# eib-generic.net
KiCad netlist of a schematic drawn in EAGLE
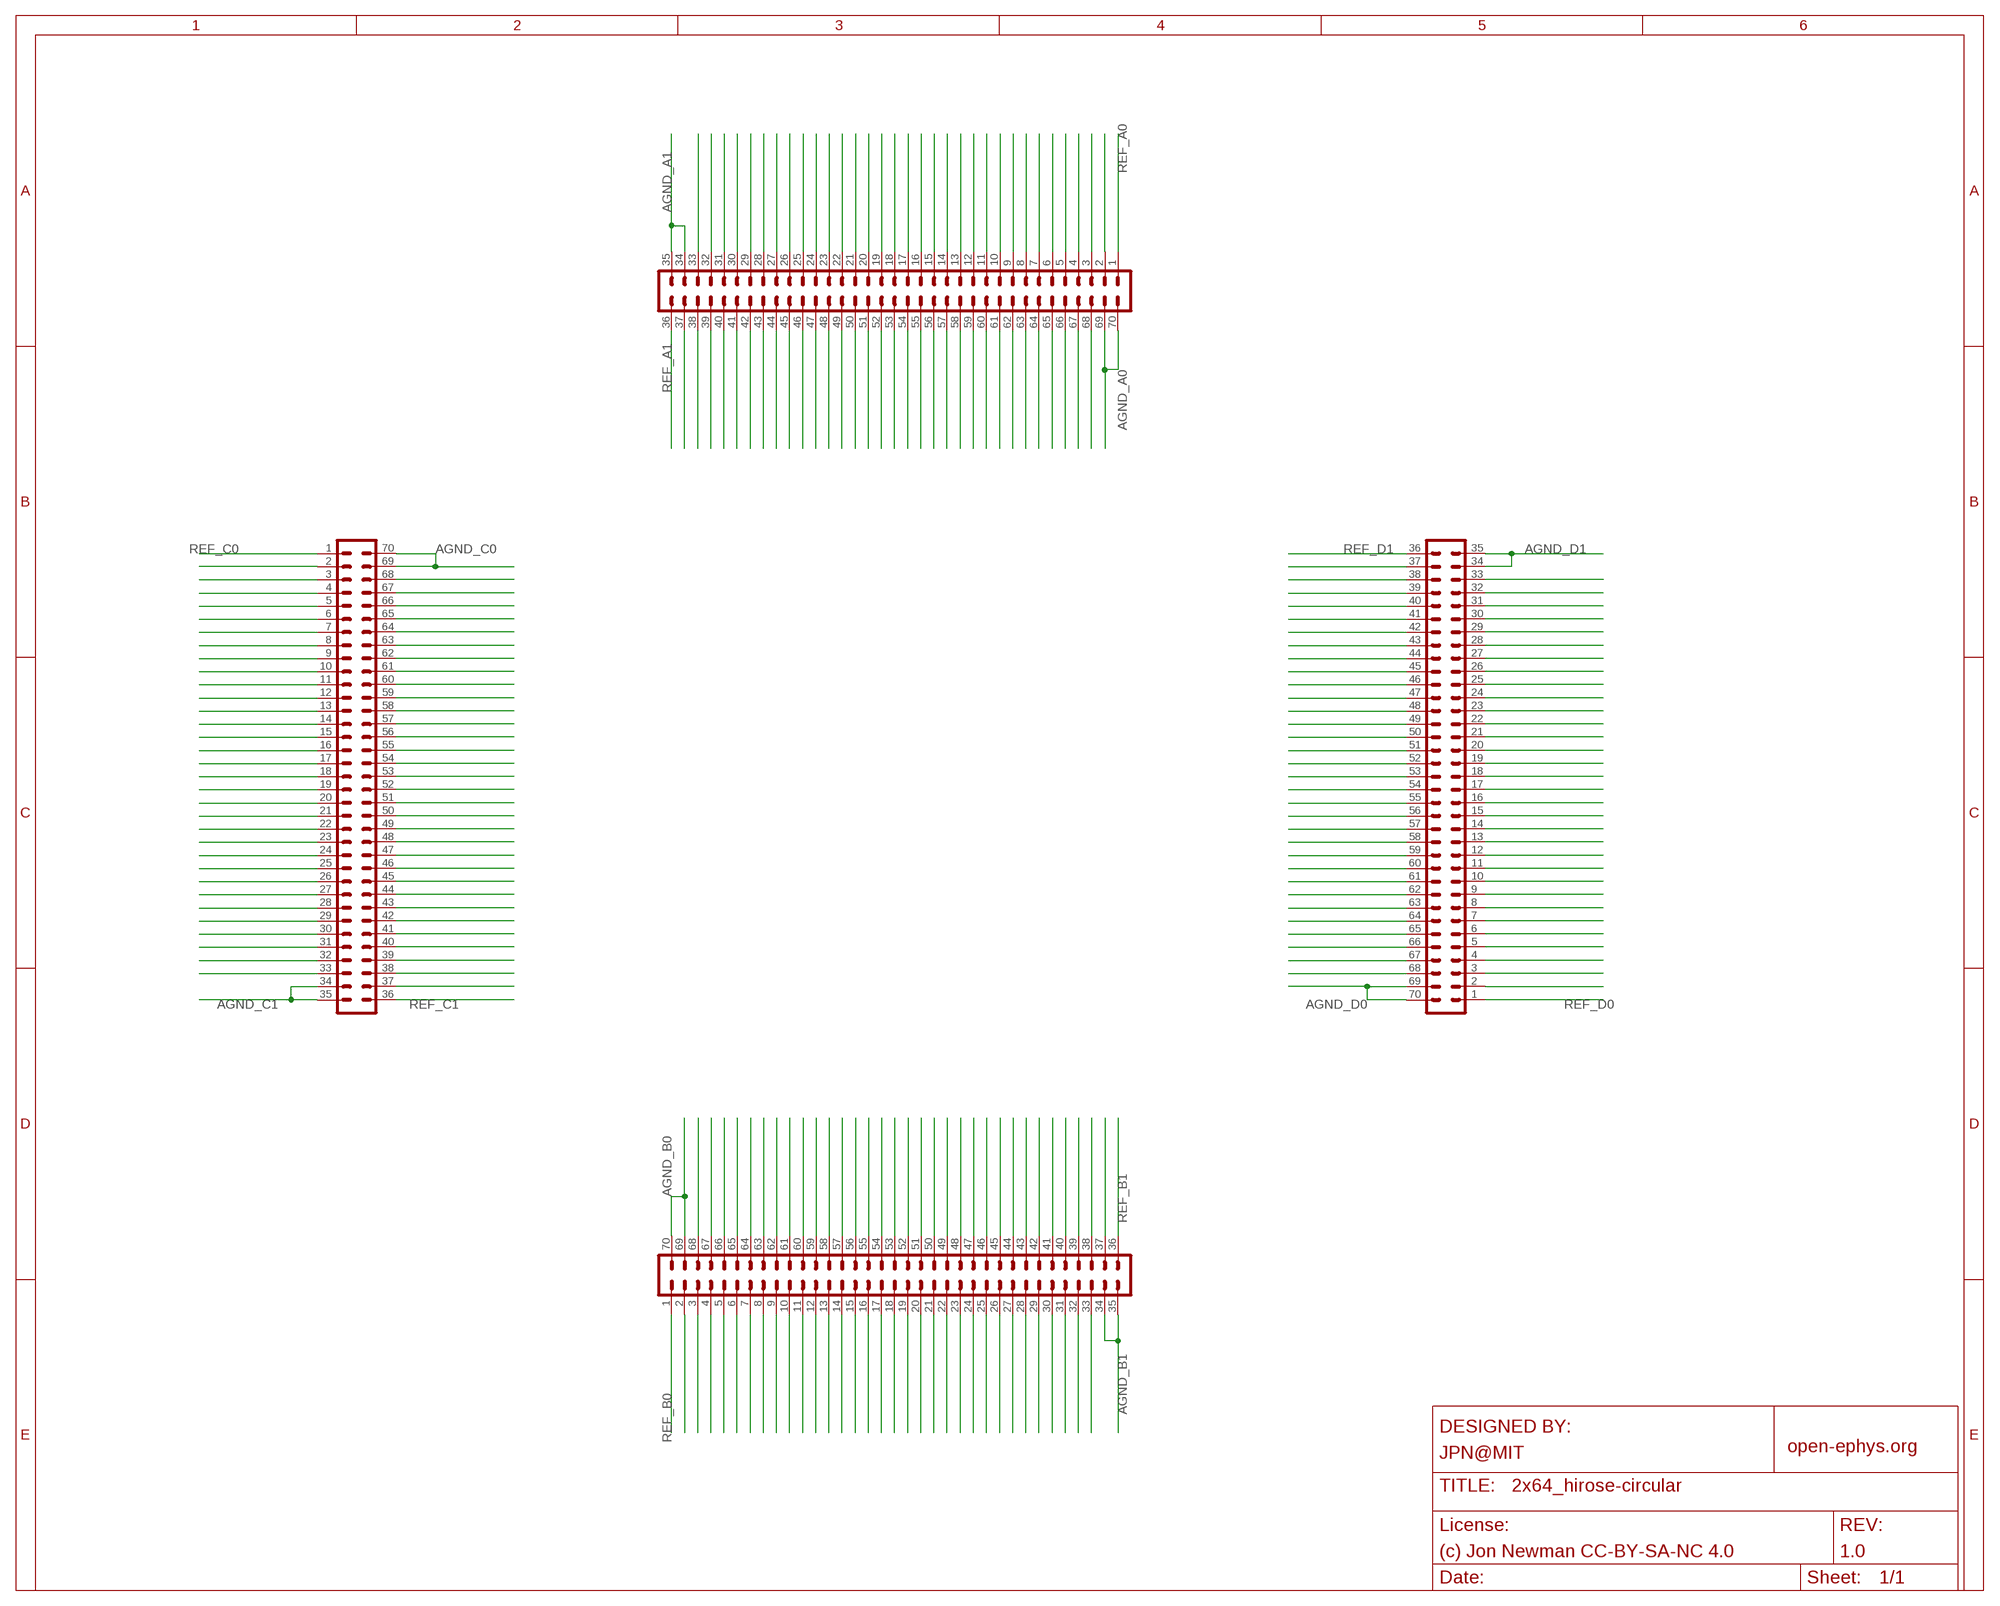
[diagram p0: schematic, sheet 1]

(export (version "E")
  (design (tool "Eeschema 10.0.6"))
  (components
    (comp (ref "A")
      (value "DF40HEAD")
      (footprint "eagle-import:DF40-70HEAD")
      (libsource (lib "eagle-import") (part "PINHD-2X35_DF40HEAD"))
    )
    (comp (ref "B")
      (value "DF40HEAD")
      (footprint "eagle-import:DF40-70HEAD")
      (libsource (lib "eagle-import") (part "PINHD-2X35_DF40HEAD"))
    )
    (comp (ref "C")
      (value "DF40HEAD")
      (footprint "eagle-import:DF40-70HEAD")
      (libsource (lib "eagle-import") (part "PINHD-2X35_DF40HEAD"))
    )
    (comp (ref "D")
      (value "DF40HEAD")
      (footprint "eagle-import:DF40-70HEAD")
      (libsource (lib "eagle-import") (part "PINHD-2X35_DF40HEAD"))
    )
  )
  (nets
    (net (code "1") (name "/AGND_A0") (class "Default")
      (node (ref "A") (pin "69") (pinfunction "69_69") (pintype "bidirectional"))
      (node (ref "A") (pin "70") (pinfunction "70_70") (pintype "bidirectional"))
    )
    (net (code "2") (name "/AGND_A1") (class "Default")
      (node (ref "A") (pin "34") (pinfunction "34_34") (pintype "bidirectional"))
      (node (ref "A") (pin "35") (pinfunction "35_35") (pintype "bidirectional"))
    )
    (net (code "3") (name "/AGND_B0") (class "Default")
      (node (ref "B") (pin "69") (pinfunction "69_69") (pintype "bidirectional"))
      (node (ref "B") (pin "70") (pinfunction "70_70") (pintype "bidirectional"))
    )
    (net (code "4") (name "/AGND_B1") (class "Default")
      (node (ref "B") (pin "34") (pinfunction "34_34") (pintype "bidirectional"))
      (node (ref "B") (pin "35") (pinfunction "35_35") (pintype "bidirectional"))
    )
    (net (code "5") (name "/AGND_C0") (class "Default")
      (node (ref "C") (pin "69") (pinfunction "69_69") (pintype "bidirectional"))
      (node (ref "C") (pin "70") (pinfunction "70_70") (pintype "bidirectional"))
    )
    (net (code "6") (name "/AGND_C1") (class "Default")
      (node (ref "C") (pin "34") (pinfunction "34_34") (pintype "bidirectional"))
      (node (ref "C") (pin "35") (pinfunction "35_35") (pintype "bidirectional"))
    )
    (net (code "7") (name "/AGND_D0") (class "Default")
      (node (ref "D") (pin "69") (pinfunction "69_69") (pintype "bidirectional"))
      (node (ref "D") (pin "70") (pinfunction "70_70") (pintype "bidirectional"))
    )
    (net (code "8") (name "/AGND_D1") (class "Default")
      (node (ref "D") (pin "34") (pinfunction "34_34") (pintype "bidirectional"))
      (node (ref "D") (pin "35") (pinfunction "35_35") (pintype "bidirectional"))
    )
    (net (code "9") (name "/REF_A0") (class "Default")
      (node (ref "A") (pin "1") (pinfunction "1_1") (pintype "bidirectional"))
    )
    (net (code "10") (name "/REF_A1") (class "Default")
      (node (ref "A") (pin "36") (pinfunction "36_36") (pintype "bidirectional"))
    )
    (net (code "11") (name "/REF_B0") (class "Default")
      (node (ref "B") (pin "1") (pinfunction "1_1") (pintype "bidirectional"))
    )
    (net (code "12") (name "/REF_B1") (class "Default")
      (node (ref "B") (pin "36") (pinfunction "36_36") (pintype "bidirectional"))
    )
    (net (code "13") (name "/REF_C0") (class "Default")
      (node (ref "C") (pin "1") (pinfunction "1_1") (pintype "bidirectional"))
    )
    (net (code "14") (name "/REF_C1") (class "Default")
      (node (ref "C") (pin "36") (pinfunction "36_36") (pintype "bidirectional"))
    )
    (net (code "15") (name "/REF_D0") (class "Default")
      (node (ref "D") (pin "1") (pinfunction "1_1") (pintype "bidirectional"))
    )
    (net (code "16") (name "/REF_D1") (class "Default")
      (node (ref "D") (pin "36") (pinfunction "36_36") (pintype "bidirectional"))
    )
    (net (code "17") (name "unconnected-(A-Pad2)") (class "Default")
      (node (ref "A") (pin "2") (pinfunction "2_2") (pintype "bidirectional"))
    )
    (net (code "18") (name "unconnected-(A-Pad3)") (class "Default")
      (node (ref "A") (pin "3") (pinfunction "3_3") (pintype "bidirectional"))
    )
    (net (code "19") (name "unconnected-(A-Pad4)") (class "Default")
      (node (ref "A") (pin "4") (pinfunction "4_4") (pintype "bidirectional"))
    )
    (net (code "20") (name "unconnected-(A-Pad5)") (class "Default")
      (node (ref "A") (pin "5") (pinfunction "5_5") (pintype "bidirectional"))
    )
    (net (code "21") (name "unconnected-(A-Pad6)") (class "Default")
      (node (ref "A") (pin "6") (pinfunction "6_6") (pintype "bidirectional"))
    )
    (net (code "22") (name "unconnected-(A-Pad7)") (class "Default")
      (node (ref "A") (pin "7") (pinfunction "7_7") (pintype "bidirectional"))
    )
    (net (code "23") (name "unconnected-(A-Pad8)") (class "Default")
      (node (ref "A") (pin "8") (pinfunction "8_8") (pintype "bidirectional"))
    )
    (net (code "24") (name "unconnected-(A-Pad9)") (class "Default")
      (node (ref "A") (pin "9") (pinfunction "9_9") (pintype "bidirectional"))
    )
    (net (code "25") (name "unconnected-(A-Pad10)") (class "Default")
      (node (ref "A") (pin "10") (pinfunction "10_10") (pintype "bidirectional"))
    )
    (net (code "26") (name "unconnected-(A-Pad11)") (class "Default")
      (node (ref "A") (pin "11") (pinfunction "11_11") (pintype "bidirectional"))
    )
    (net (code "27") (name "unconnected-(A-Pad12)") (class "Default")
      (node (ref "A") (pin "12") (pinfunction "12_12") (pintype "bidirectional"))
    )
    (net (code "28") (name "unconnected-(A-Pad13)") (class "Default")
      (node (ref "A") (pin "13") (pinfunction "13_13") (pintype "bidirectional"))
    )
    (net (code "29") (name "unconnected-(A-Pad14)") (class "Default")
      (node (ref "A") (pin "14") (pinfunction "14_14") (pintype "bidirectional"))
    )
    (net (code "30") (name "unconnected-(A-Pad15)") (class "Default")
      (node (ref "A") (pin "15") (pinfunction "15_15") (pintype "bidirectional"))
    )
    (net (code "31") (name "unconnected-(A-Pad16)") (class "Default")
      (node (ref "A") (pin "16") (pinfunction "16_16") (pintype "bidirectional"))
    )
    (net (code "32") (name "unconnected-(A-Pad17)") (class "Default")
      (node (ref "A") (pin "17") (pinfunction "17_17") (pintype "bidirectional"))
    )
    (net (code "33") (name "unconnected-(A-Pad18)") (class "Default")
      (node (ref "A") (pin "18") (pinfunction "18_18") (pintype "bidirectional"))
    )
    (net (code "34") (name "unconnected-(A-Pad19)") (class "Default")
      (node (ref "A") (pin "19") (pinfunction "19_19") (pintype "bidirectional"))
    )
    (net (code "35") (name "unconnected-(A-Pad20)") (class "Default")
      (node (ref "A") (pin "20") (pinfunction "20_20") (pintype "bidirectional"))
    )
    (net (code "36") (name "unconnected-(A-Pad21)") (class "Default")
      (node (ref "A") (pin "21") (pinfunction "21_21") (pintype "bidirectional"))
    )
    (net (code "37") (name "unconnected-(A-Pad22)") (class "Default")
      (node (ref "A") (pin "22") (pinfunction "22_22") (pintype "bidirectional"))
    )
    (net (code "38") (name "unconnected-(A-Pad23)") (class "Default")
      (node (ref "A") (pin "23") (pinfunction "23_23") (pintype "bidirectional"))
    )
    (net (code "39") (name "unconnected-(A-Pad24)") (class "Default")
      (node (ref "A") (pin "24") (pinfunction "24_24") (pintype "bidirectional"))
    )
    (net (code "40") (name "unconnected-(A-Pad25)") (class "Default")
      (node (ref "A") (pin "25") (pinfunction "25_25") (pintype "bidirectional"))
    )
    (net (code "41") (name "unconnected-(A-Pad26)") (class "Default")
      (node (ref "A") (pin "26") (pinfunction "26_26") (pintype "bidirectional"))
    )
    (net (code "42") (name "unconnected-(A-Pad27)") (class "Default")
      (node (ref "A") (pin "27") (pinfunction "27_27") (pintype "bidirectional"))
    )
    (net (code "43") (name "unconnected-(A-Pad28)") (class "Default")
      (node (ref "A") (pin "28") (pinfunction "28_28") (pintype "bidirectional"))
    )
    (net (code "44") (name "unconnected-(A-Pad29)") (class "Default")
      (node (ref "A") (pin "29") (pinfunction "29_29") (pintype "bidirectional"))
    )
    (net (code "45") (name "unconnected-(A-Pad30)") (class "Default")
      (node (ref "A") (pin "30") (pinfunction "30_30") (pintype "bidirectional"))
    )
    (net (code "46") (name "unconnected-(A-Pad31)") (class "Default")
      (node (ref "A") (pin "31") (pinfunction "31_31") (pintype "bidirectional"))
    )
    (net (code "47") (name "unconnected-(A-Pad32)") (class "Default")
      (node (ref "A") (pin "32") (pinfunction "32_32") (pintype "bidirectional"))
    )
    (net (code "48") (name "unconnected-(A-Pad33)") (class "Default")
      (node (ref "A") (pin "33") (pinfunction "33_33") (pintype "bidirectional"))
    )
    (net (code "49") (name "unconnected-(A-Pad37)") (class "Default")
      (node (ref "A") (pin "37") (pinfunction "37_37") (pintype "bidirectional"))
    )
    (net (code "50") (name "unconnected-(A-Pad38)") (class "Default")
      (node (ref "A") (pin "38") (pinfunction "38_38") (pintype "bidirectional"))
    )
    (net (code "51") (name "unconnected-(A-Pad39)") (class "Default")
      (node (ref "A") (pin "39") (pinfunction "39_39") (pintype "bidirectional"))
    )
    (net (code "52") (name "unconnected-(A-Pad40)") (class "Default")
      (node (ref "A") (pin "40") (pinfunction "40_40") (pintype "bidirectional"))
    )
    (net (code "53") (name "unconnected-(A-Pad41)") (class "Default")
      (node (ref "A") (pin "41") (pinfunction "41_41") (pintype "bidirectional"))
    )
    (net (code "54") (name "unconnected-(A-Pad42)") (class "Default")
      (node (ref "A") (pin "42") (pinfunction "42_42") (pintype "bidirectional"))
    )
    (net (code "55") (name "unconnected-(A-Pad43)") (class "Default")
      (node (ref "A") (pin "43") (pinfunction "43_43") (pintype "bidirectional"))
    )
    (net (code "56") (name "unconnected-(A-Pad44)") (class "Default")
      (node (ref "A") (pin "44") (pinfunction "44_44") (pintype "bidirectional"))
    )
    (net (code "57") (name "unconnected-(A-Pad45)") (class "Default")
      (node (ref "A") (pin "45") (pinfunction "45_45") (pintype "bidirectional"))
    )
    (net (code "58") (name "unconnected-(A-Pad46)") (class "Default")
      (node (ref "A") (pin "46") (pinfunction "46_46") (pintype "bidirectional"))
    )
    (net (code "59") (name "unconnected-(A-Pad47)") (class "Default")
      (node (ref "A") (pin "47") (pinfunction "47_47") (pintype "bidirectional"))
    )
    (net (code "60") (name "unconnected-(A-Pad48)") (class "Default")
      (node (ref "A") (pin "48") (pinfunction "48_48") (pintype "bidirectional"))
    )
    (net (code "61") (name "unconnected-(A-Pad49)") (class "Default")
      (node (ref "A") (pin "49") (pinfunction "49_49") (pintype "bidirectional"))
    )
    (net (code "62") (name "unconnected-(A-Pad50)") (class "Default")
      (node (ref "A") (pin "50") (pinfunction "50_50") (pintype "bidirectional"))
    )
    (net (code "63") (name "unconnected-(A-Pad51)") (class "Default")
      (node (ref "A") (pin "51") (pinfunction "51_51") (pintype "bidirectional"))
    )
    (net (code "64") (name "unconnected-(A-Pad52)") (class "Default")
      (node (ref "A") (pin "52") (pinfunction "52_52") (pintype "bidirectional"))
    )
    (net (code "65") (name "unconnected-(A-Pad53)") (class "Default")
      (node (ref "A") (pin "53") (pinfunction "53_53") (pintype "bidirectional"))
    )
    (net (code "66") (name "unconnected-(A-Pad54)") (class "Default")
      (node (ref "A") (pin "54") (pinfunction "54_54") (pintype "bidirectional"))
    )
    (net (code "67") (name "unconnected-(A-Pad55)") (class "Default")
      (node (ref "A") (pin "55") (pinfunction "55_55") (pintype "bidirectional"))
    )
    (net (code "68") (name "unconnected-(A-Pad56)") (class "Default")
      (node (ref "A") (pin "56") (pinfunction "56_56") (pintype "bidirectional"))
    )
    (net (code "69") (name "unconnected-(A-Pad57)") (class "Default")
      (node (ref "A") (pin "57") (pinfunction "57_57") (pintype "bidirectional"))
    )
    (net (code "70") (name "unconnected-(A-Pad58)") (class "Default")
      (node (ref "A") (pin "58") (pinfunction "58_58") (pintype "bidirectional"))
    )
    (net (code "71") (name "unconnected-(A-Pad59)") (class "Default")
      (node (ref "A") (pin "59") (pinfunction "59_59") (pintype "bidirectional"))
    )
    (net (code "72") (name "unconnected-(A-Pad60)") (class "Default")
      (node (ref "A") (pin "60") (pinfunction "60_60") (pintype "bidirectional"))
    )
    (net (code "73") (name "unconnected-(A-Pad61)") (class "Default")
      (node (ref "A") (pin "61") (pinfunction "61_61") (pintype "bidirectional"))
    )
    (net (code "74") (name "unconnected-(A-Pad62)") (class "Default")
      (node (ref "A") (pin "62") (pinfunction "62_62") (pintype "bidirectional"))
    )
    (net (code "75") (name "unconnected-(A-Pad63)") (class "Default")
      (node (ref "A") (pin "63") (pinfunction "63_63") (pintype "bidirectional"))
    )
    (net (code "76") (name "unconnected-(A-Pad64)") (class "Default")
      (node (ref "A") (pin "64") (pinfunction "64_64") (pintype "bidirectional"))
    )
    (net (code "77") (name "unconnected-(A-Pad65)") (class "Default")
      (node (ref "A") (pin "65") (pinfunction "65_65") (pintype "bidirectional"))
    )
    (net (code "78") (name "unconnected-(A-Pad66)") (class "Default")
      (node (ref "A") (pin "66") (pinfunction "66_66") (pintype "bidirectional"))
    )
    (net (code "79") (name "unconnected-(A-Pad67)") (class "Default")
      (node (ref "A") (pin "67") (pinfunction "67_67") (pintype "bidirectional"))
    )
    (net (code "80") (name "unconnected-(A-Pad68)") (class "Default")
      (node (ref "A") (pin "68") (pinfunction "68_68") (pintype "bidirectional"))
    )
    (net (code "81") (name "unconnected-(B-Pad2)") (class "Default")
      (node (ref "B") (pin "2") (pinfunction "2_2") (pintype "bidirectional"))
    )
    (net (code "82") (name "unconnected-(B-Pad3)") (class "Default")
      (node (ref "B") (pin "3") (pinfunction "3_3") (pintype "bidirectional"))
    )
    (net (code "83") (name "unconnected-(B-Pad4)") (class "Default")
      (node (ref "B") (pin "4") (pinfunction "4_4") (pintype "bidirectional"))
    )
    (net (code "84") (name "unconnected-(B-Pad5)") (class "Default")
      (node (ref "B") (pin "5") (pinfunction "5_5") (pintype "bidirectional"))
    )
    (net (code "85") (name "unconnected-(B-Pad6)") (class "Default")
      (node (ref "B") (pin "6") (pinfunction "6_6") (pintype "bidirectional"))
    )
    (net (code "86") (name "unconnected-(B-Pad7)") (class "Default")
      (node (ref "B") (pin "7") (pinfunction "7_7") (pintype "bidirectional"))
    )
    (net (code "87") (name "unconnected-(B-Pad8)") (class "Default")
      (node (ref "B") (pin "8") (pinfunction "8_8") (pintype "bidirectional"))
    )
    (net (code "88") (name "unconnected-(B-Pad9)") (class "Default")
      (node (ref "B") (pin "9") (pinfunction "9_9") (pintype "bidirectional"))
    )
    (net (code "89") (name "unconnected-(B-Pad10)") (class "Default")
      (node (ref "B") (pin "10") (pinfunction "10_10") (pintype "bidirectional"))
    )
    (net (code "90") (name "unconnected-(B-Pad11)") (class "Default")
      (node (ref "B") (pin "11") (pinfunction "11_11") (pintype "bidirectional"))
    )
    (net (code "91") (name "unconnected-(B-Pad12)") (class "Default")
      (node (ref "B") (pin "12") (pinfunction "12_12") (pintype "bidirectional"))
    )
    (net (code "92") (name "unconnected-(B-Pad13)") (class "Default")
      (node (ref "B") (pin "13") (pinfunction "13_13") (pintype "bidirectional"))
    )
    (net (code "93") (name "unconnected-(B-Pad14)") (class "Default")
      (node (ref "B") (pin "14") (pinfunction "14_14") (pintype "bidirectional"))
    )
    (net (code "94") (name "unconnected-(B-Pad15)") (class "Default")
      (node (ref "B") (pin "15") (pinfunction "15_15") (pintype "bidirectional"))
    )
    (net (code "95") (name "unconnected-(B-Pad16)") (class "Default")
      (node (ref "B") (pin "16") (pinfunction "16_16") (pintype "bidirectional"))
    )
    (net (code "96") (name "unconnected-(B-Pad17)") (class "Default")
      (node (ref "B") (pin "17") (pinfunction "17_17") (pintype "bidirectional"))
    )
    (net (code "97") (name "unconnected-(B-Pad18)") (class "Default")
      (node (ref "B") (pin "18") (pinfunction "18_18") (pintype "bidirectional"))
    )
    (net (code "98") (name "unconnected-(B-Pad19)") (class "Default")
      (node (ref "B") (pin "19") (pinfunction "19_19") (pintype "bidirectional"))
    )
    (net (code "99") (name "unconnected-(B-Pad20)") (class "Default")
      (node (ref "B") (pin "20") (pinfunction "20_20") (pintype "bidirectional"))
    )
    (net (code "100") (name "unconnected-(B-Pad21)") (class "Default")
      (node (ref "B") (pin "21") (pinfunction "21_21") (pintype "bidirectional"))
    )
    (net (code "101") (name "unconnected-(B-Pad22)") (class "Default")
      (node (ref "B") (pin "22") (pinfunction "22_22") (pintype "bidirectional"))
    )
    (net (code "102") (name "unconnected-(B-Pad23)") (class "Default")
      (node (ref "B") (pin "23") (pinfunction "23_23") (pintype "bidirectional"))
    )
    (net (code "103") (name "unconnected-(B-Pad24)") (class "Default")
      (node (ref "B") (pin "24") (pinfunction "24_24") (pintype "bidirectional"))
    )
    (net (code "104") (name "unconnected-(B-Pad25)") (class "Default")
      (node (ref "B") (pin "25") (pinfunction "25_25") (pintype "bidirectional"))
    )
    (net (code "105") (name "unconnected-(B-Pad26)") (class "Default")
      (node (ref "B") (pin "26") (pinfunction "26_26") (pintype "bidirectional"))
    )
    (net (code "106") (name "unconnected-(B-Pad27)") (class "Default")
      (node (ref "B") (pin "27") (pinfunction "27_27") (pintype "bidirectional"))
    )
    (net (code "107") (name "unconnected-(B-Pad28)") (class "Default")
      (node (ref "B") (pin "28") (pinfunction "28_28") (pintype "bidirectional"))
    )
    (net (code "108") (name "unconnected-(B-Pad29)") (class "Default")
      (node (ref "B") (pin "29") (pinfunction "29_29") (pintype "bidirectional"))
    )
    (net (code "109") (name "unconnected-(B-Pad30)") (class "Default")
      (node (ref "B") (pin "30") (pinfunction "30_30") (pintype "bidirectional"))
    )
    (net (code "110") (name "unconnected-(B-Pad31)") (class "Default")
      (node (ref "B") (pin "31") (pinfunction "31_31") (pintype "bidirectional"))
    )
    (net (code "111") (name "unconnected-(B-Pad32)") (class "Default")
      (node (ref "B") (pin "32") (pinfunction "32_32") (pintype "bidirectional"))
    )
    (net (code "112") (name "unconnected-(B-Pad33)") (class "Default")
      (node (ref "B") (pin "33") (pinfunction "33_33") (pintype "bidirectional"))
    )
    (net (code "113") (name "unconnected-(B-Pad37)") (class "Default")
      (node (ref "B") (pin "37") (pinfunction "37_37") (pintype "bidirectional"))
    )
    (net (code "114") (name "unconnected-(B-Pad38)") (class "Default")
      (node (ref "B") (pin "38") (pinfunction "38_38") (pintype "bidirectional"))
    )
    (net (code "115") (name "unconnected-(B-Pad39)") (class "Default")
      (node (ref "B") (pin "39") (pinfunction "39_39") (pintype "bidirectional"))
    )
    (net (code "116") (name "unconnected-(B-Pad40)") (class "Default")
      (node (ref "B") (pin "40") (pinfunction "40_40") (pintype "bidirectional"))
    )
    (net (code "117") (name "unconnected-(B-Pad41)") (class "Default")
      (node (ref "B") (pin "41") (pinfunction "41_41") (pintype "bidirectional"))
    )
    (net (code "118") (name "unconnected-(B-Pad42)") (class "Default")
      (node (ref "B") (pin "42") (pinfunction "42_42") (pintype "bidirectional"))
    )
    (net (code "119") (name "unconnected-(B-Pad43)") (class "Default")
      (node (ref "B") (pin "43") (pinfunction "43_43") (pintype "bidirectional"))
    )
    (net (code "120") (name "unconnected-(B-Pad44)") (class "Default")
      (node (ref "B") (pin "44") (pinfunction "44_44") (pintype "bidirectional"))
    )
    (net (code "121") (name "unconnected-(B-Pad45)") (class "Default")
      (node (ref "B") (pin "45") (pinfunction "45_45") (pintype "bidirectional"))
    )
    (net (code "122") (name "unconnected-(B-Pad46)") (class "Default")
      (node (ref "B") (pin "46") (pinfunction "46_46") (pintype "bidirectional"))
    )
    (net (code "123") (name "unconnected-(B-Pad47)") (class "Default")
      (node (ref "B") (pin "47") (pinfunction "47_47") (pintype "bidirectional"))
    )
    (net (code "124") (name "unconnected-(B-Pad48)") (class "Default")
      (node (ref "B") (pin "48") (pinfunction "48_48") (pintype "bidirectional"))
    )
    (net (code "125") (name "unconnected-(B-Pad49)") (class "Default")
      (node (ref "B") (pin "49") (pinfunction "49_49") (pintype "bidirectional"))
    )
    (net (code "126") (name "unconnected-(B-Pad50)") (class "Default")
      (node (ref "B") (pin "50") (pinfunction "50_50") (pintype "bidirectional"))
    )
    (net (code "127") (name "unconnected-(B-Pad51)") (class "Default")
      (node (ref "B") (pin "51") (pinfunction "51_51") (pintype "bidirectional"))
    )
    (net (code "128") (name "unconnected-(B-Pad52)") (class "Default")
      (node (ref "B") (pin "52") (pinfunction "52_52") (pintype "bidirectional"))
    )
    (net (code "129") (name "unconnected-(B-Pad53)") (class "Default")
      (node (ref "B") (pin "53") (pinfunction "53_53") (pintype "bidirectional"))
    )
    (net (code "130") (name "unconnected-(B-Pad54)") (class "Default")
      (node (ref "B") (pin "54") (pinfunction "54_54") (pintype "bidirectional"))
    )
    (net (code "131") (name "unconnected-(B-Pad55)") (class "Default")
      (node (ref "B") (pin "55") (pinfunction "55_55") (pintype "bidirectional"))
    )
    (net (code "132") (name "unconnected-(B-Pad56)") (class "Default")
      (node (ref "B") (pin "56") (pinfunction "56_56") (pintype "bidirectional"))
    )
    (net (code "133") (name "unconnected-(B-Pad57)") (class "Default")
      (node (ref "B") (pin "57") (pinfunction "57_57") (pintype "bidirectional"))
    )
    (net (code "134") (name "unconnected-(B-Pad58)") (class "Default")
      (node (ref "B") (pin "58") (pinfunction "58_58") (pintype "bidirectional"))
    )
    (net (code "135") (name "unconnected-(B-Pad59)") (class "Default")
      (node (ref "B") (pin "59") (pinfunction "59_59") (pintype "bidirectional"))
    )
    (net (code "136") (name "unconnected-(B-Pad60)") (class "Default")
      (node (ref "B") (pin "60") (pinfunction "60_60") (pintype "bidirectional"))
    )
    (net (code "137") (name "unconnected-(B-Pad61)") (class "Default")
      (node (ref "B") (pin "61") (pinfunction "61_61") (pintype "bidirectional"))
    )
    (net (code "138") (name "unconnected-(B-Pad62)") (class "Default")
      (node (ref "B") (pin "62") (pinfunction "62_62") (pintype "bidirectional"))
    )
    (net (code "139") (name "unconnected-(B-Pad63)") (class "Default")
      (node (ref "B") (pin "63") (pinfunction "63_63") (pintype "bidirectional"))
    )
    (net (code "140") (name "unconnected-(B-Pad64)") (class "Default")
      (node (ref "B") (pin "64") (pinfunction "64_64") (pintype "bidirectional"))
    )
    (net (code "141") (name "unconnected-(B-Pad65)") (class "Default")
      (node (ref "B") (pin "65") (pinfunction "65_65") (pintype "bidirectional"))
    )
    (net (code "142") (name "unconnected-(B-Pad66)") (class "Default")
      (node (ref "B") (pin "66") (pinfunction "66_66") (pintype "bidirectional"))
    )
    (net (code "143") (name "unconnected-(B-Pad67)") (class "Default")
      (node (ref "B") (pin "67") (pinfunction "67_67") (pintype "bidirectional"))
    )
    (net (code "144") (name "unconnected-(B-Pad68)") (class "Default")
      (node (ref "B") (pin "68") (pinfunction "68_68") (pintype "bidirectional"))
    )
    (net (code "145") (name "unconnected-(C-Pad2)") (class "Default")
      (node (ref "C") (pin "2") (pinfunction "2_2") (pintype "bidirectional"))
    )
    (net (code "146") (name "unconnected-(C-Pad3)") (class "Default")
      (node (ref "C") (pin "3") (pinfunction "3_3") (pintype "bidirectional"))
    )
    (net (code "147") (name "unconnected-(C-Pad4)") (class "Default")
      (node (ref "C") (pin "4") (pinfunction "4_4") (pintype "bidirectional"))
    )
    (net (code "148") (name "unconnected-(C-Pad5)") (class "Default")
      (node (ref "C") (pin "5") (pinfunction "5_5") (pintype "bidirectional"))
    )
    (net (code "149") (name "unconnected-(C-Pad6)") (class "Default")
      (node (ref "C") (pin "6") (pinfunction "6_6") (pintype "bidirectional"))
    )
    (net (code "150") (name "unconnected-(C-Pad7)") (class "Default")
      (node (ref "C") (pin "7") (pinfunction "7_7") (pintype "bidirectional"))
    )
    (net (code "151") (name "unconnected-(C-Pad8)") (class "Default")
      (node (ref "C") (pin "8") (pinfunction "8_8") (pintype "bidirectional"))
    )
    (net (code "152") (name "unconnected-(C-Pad9)") (class "Default")
      (node (ref "C") (pin "9") (pinfunction "9_9") (pintype "bidirectional"))
    )
    (net (code "153") (name "unconnected-(C-Pad10)") (class "Default")
      (node (ref "C") (pin "10") (pinfunction "10_10") (pintype "bidirectional"))
    )
    (net (code "154") (name "unconnected-(C-Pad11)") (class "Default")
      (node (ref "C") (pin "11") (pinfunction "11_11") (pintype "bidirectional"))
    )
    (net (code "155") (name "unconnected-(C-Pad12)") (class "Default")
      (node (ref "C") (pin "12") (pinfunction "12_12") (pintype "bidirectional"))
    )
    (net (code "156") (name "unconnected-(C-Pad13)") (class "Default")
      (node (ref "C") (pin "13") (pinfunction "13_13") (pintype "bidirectional"))
    )
    (net (code "157") (name "unconnected-(C-Pad14)") (class "Default")
      (node (ref "C") (pin "14") (pinfunction "14_14") (pintype "bidirectional"))
    )
    (net (code "158") (name "unconnected-(C-Pad15)") (class "Default")
      (node (ref "C") (pin "15") (pinfunction "15_15") (pintype "bidirectional"))
    )
    (net (code "159") (name "unconnected-(C-Pad16)") (class "Default")
      (node (ref "C") (pin "16") (pinfunction "16_16") (pintype "bidirectional"))
    )
    (net (code "160") (name "unconnected-(C-Pad17)") (class "Default")
      (node (ref "C") (pin "17") (pinfunction "17_17") (pintype "bidirectional"))
    )
    (net (code "161") (name "unconnected-(C-Pad18)") (class "Default")
      (node (ref "C") (pin "18") (pinfunction "18_18") (pintype "bidirectional"))
    )
    (net (code "162") (name "unconnected-(C-Pad19)") (class "Default")
      (node (ref "C") (pin "19") (pinfunction "19_19") (pintype "bidirectional"))
    )
    (net (code "163") (name "unconnected-(C-Pad20)") (class "Default")
      (node (ref "C") (pin "20") (pinfunction "20_20") (pintype "bidirectional"))
    )
    (net (code "164") (name "unconnected-(C-Pad21)") (class "Default")
      (node (ref "C") (pin "21") (pinfunction "21_21") (pintype "bidirectional"))
    )
    (net (code "165") (name "unconnected-(C-Pad22)") (class "Default")
      (node (ref "C") (pin "22") (pinfunction "22_22") (pintype "bidirectional"))
    )
    (net (code "166") (name "unconnected-(C-Pad23)") (class "Default")
      (node (ref "C") (pin "23") (pinfunction "23_23") (pintype "bidirectional"))
    )
    (net (code "167") (name "unconnected-(C-Pad24)") (class "Default")
      (node (ref "C") (pin "24") (pinfunction "24_24") (pintype "bidirectional"))
    )
    (net (code "168") (name "unconnected-(C-Pad25)") (class "Default")
      (node (ref "C") (pin "25") (pinfunction "25_25") (pintype "bidirectional"))
    )
    (net (code "169") (name "unconnected-(C-Pad26)") (class "Default")
      (node (ref "C") (pin "26") (pinfunction "26_26") (pintype "bidirectional"))
    )
    (net (code "170") (name "unconnected-(C-Pad27)") (class "Default")
      (node (ref "C") (pin "27") (pinfunction "27_27") (pintype "bidirectional"))
    )
    (net (code "171") (name "unconnected-(C-Pad28)") (class "Default")
      (node (ref "C") (pin "28") (pinfunction "28_28") (pintype "bidirectional"))
    )
    (net (code "172") (name "unconnected-(C-Pad29)") (class "Default")
      (node (ref "C") (pin "29") (pinfunction "29_29") (pintype "bidirectional"))
    )
    (net (code "173") (name "unconnected-(C-Pad30)") (class "Default")
      (node (ref "C") (pin "30") (pinfunction "30_30") (pintype "bidirectional"))
    )
    (net (code "174") (name "unconnected-(C-Pad31)") (class "Default")
      (node (ref "C") (pin "31") (pinfunction "31_31") (pintype "bidirectional"))
    )
    (net (code "175") (name "unconnected-(C-Pad32)") (class "Default")
      (node (ref "C") (pin "32") (pinfunction "32_32") (pintype "bidirectional"))
    )
    (net (code "176") (name "unconnected-(C-Pad33)") (class "Default")
      (node (ref "C") (pin "33") (pinfunction "33_33") (pintype "bidirectional"))
    )
    (net (code "177") (name "unconnected-(C-Pad37)") (class "Default")
      (node (ref "C") (pin "37") (pinfunction "37_37") (pintype "bidirectional"))
    )
    (net (code "178") (name "unconnected-(C-Pad38)") (class "Default")
      (node (ref "C") (pin "38") (pinfunction "38_38") (pintype "bidirectional"))
    )
    (net (code "179") (name "unconnected-(C-Pad39)") (class "Default")
      (node (ref "C") (pin "39") (pinfunction "39_39") (pintype "bidirectional"))
    )
    (net (code "180") (name "unconnected-(C-Pad40)") (class "Default")
      (node (ref "C") (pin "40") (pinfunction "40_40") (pintype "bidirectional"))
    )
    (net (code "181") (name "unconnected-(C-Pad41)") (class "Default")
      (node (ref "C") (pin "41") (pinfunction "41_41") (pintype "bidirectional"))
    )
    (net (code "182") (name "unconnected-(C-Pad42)") (class "Default")
      (node (ref "C") (pin "42") (pinfunction "42_42") (pintype "bidirectional"))
    )
    (net (code "183") (name "unconnected-(C-Pad43)") (class "Default")
      (node (ref "C") (pin "43") (pinfunction "43_43") (pintype "bidirectional"))
    )
    (net (code "184") (name "unconnected-(C-Pad44)") (class "Default")
      (node (ref "C") (pin "44") (pinfunction "44_44") (pintype "bidirectional"))
    )
    (net (code "185") (name "unconnected-(C-Pad45)") (class "Default")
      (node (ref "C") (pin "45") (pinfunction "45_45") (pintype "bidirectional"))
    )
    (net (code "186") (name "unconnected-(C-Pad46)") (class "Default")
      (node (ref "C") (pin "46") (pinfunction "46_46") (pintype "bidirectional"))
    )
    (net (code "187") (name "unconnected-(C-Pad47)") (class "Default")
      (node (ref "C") (pin "47") (pinfunction "47_47") (pintype "bidirectional"))
    )
    (net (code "188") (name "unconnected-(C-Pad48)") (class "Default")
      (node (ref "C") (pin "48") (pinfunction "48_48") (pintype "bidirectional"))
    )
    (net (code "189") (name "unconnected-(C-Pad49)") (class "Default")
      (node (ref "C") (pin "49") (pinfunction "49_49") (pintype "bidirectional"))
    )
    (net (code "190") (name "unconnected-(C-Pad50)") (class "Default")
      (node (ref "C") (pin "50") (pinfunction "50_50") (pintype "bidirectional"))
    )
    (net (code "191") (name "unconnected-(C-Pad51)") (class "Default")
      (node (ref "C") (pin "51") (pinfunction "51_51") (pintype "bidirectional"))
    )
    (net (code "192") (name "unconnected-(C-Pad52)") (class "Default")
      (node (ref "C") (pin "52") (pinfunction "52_52") (pintype "bidirectional"))
    )
    (net (code "193") (name "unconnected-(C-Pad53)") (class "Default")
      (node (ref "C") (pin "53") (pinfunction "53_53") (pintype "bidirectional"))
    )
    (net (code "194") (name "unconnected-(C-Pad54)") (class "Default")
      (node (ref "C") (pin "54") (pinfunction "54_54") (pintype "bidirectional"))
    )
    (net (code "195") (name "unconnected-(C-Pad55)") (class "Default")
      (node (ref "C") (pin "55") (pinfunction "55_55") (pintype "bidirectional"))
    )
    (net (code "196") (name "unconnected-(C-Pad56)") (class "Default")
      (node (ref "C") (pin "56") (pinfunction "56_56") (pintype "bidirectional"))
    )
    (net (code "197") (name "unconnected-(C-Pad57)") (class "Default")
      (node (ref "C") (pin "57") (pinfunction "57_57") (pintype "bidirectional"))
    )
    (net (code "198") (name "unconnected-(C-Pad58)") (class "Default")
      (node (ref "C") (pin "58") (pinfunction "58_58") (pintype "bidirectional"))
    )
    (net (code "199") (name "unconnected-(C-Pad59)") (class "Default")
      (node (ref "C") (pin "59") (pinfunction "59_59") (pintype "bidirectional"))
    )
    (net (code "200") (name "unconnected-(C-Pad60)") (class "Default")
      (node (ref "C") (pin "60") (pinfunction "60_60") (pintype "bidirectional"))
    )
    (net (code "201") (name "unconnected-(C-Pad61)") (class "Default")
      (node (ref "C") (pin "61") (pinfunction "61_61") (pintype "bidirectional"))
    )
    (net (code "202") (name "unconnected-(C-Pad62)") (class "Default")
      (node (ref "C") (pin "62") (pinfunction "62_62") (pintype "bidirectional"))
    )
    (net (code "203") (name "unconnected-(C-Pad63)") (class "Default")
      (node (ref "C") (pin "63") (pinfunction "63_63") (pintype "bidirectional"))
    )
    (net (code "204") (name "unconnected-(C-Pad64)") (class "Default")
      (node (ref "C") (pin "64") (pinfunction "64_64") (pintype "bidirectional"))
    )
    (net (code "205") (name "unconnected-(C-Pad65)") (class "Default")
      (node (ref "C") (pin "65") (pinfunction "65_65") (pintype "bidirectional"))
    )
    (net (code "206") (name "unconnected-(C-Pad66)") (class "Default")
      (node (ref "C") (pin "66") (pinfunction "66_66") (pintype "bidirectional"))
    )
    (net (code "207") (name "unconnected-(C-Pad67)") (class "Default")
      (node (ref "C") (pin "67") (pinfunction "67_67") (pintype "bidirectional"))
    )
    (net (code "208") (name "unconnected-(C-Pad68)") (class "Default")
      (node (ref "C") (pin "68") (pinfunction "68_68") (pintype "bidirectional"))
    )
    (net (code "209") (name "unconnected-(D-Pad2)") (class "Default")
      (node (ref "D") (pin "2") (pinfunction "2_2") (pintype "bidirectional"))
    )
    (net (code "210") (name "unconnected-(D-Pad3)") (class "Default")
      (node (ref "D") (pin "3") (pinfunction "3_3") (pintype "bidirectional"))
    )
    (net (code "211") (name "unconnected-(D-Pad4)") (class "Default")
      (node (ref "D") (pin "4") (pinfunction "4_4") (pintype "bidirectional"))
    )
    (net (code "212") (name "unconnected-(D-Pad5)") (class "Default")
      (node (ref "D") (pin "5") (pinfunction "5_5") (pintype "bidirectional"))
    )
    (net (code "213") (name "unconnected-(D-Pad6)") (class "Default")
      (node (ref "D") (pin "6") (pinfunction "6_6") (pintype "bidirectional"))
    )
    (net (code "214") (name "unconnected-(D-Pad7)") (class "Default")
      (node (ref "D") (pin "7") (pinfunction "7_7") (pintype "bidirectional"))
    )
    (net (code "215") (name "unconnected-(D-Pad8)") (class "Default")
      (node (ref "D") (pin "8") (pinfunction "8_8") (pintype "bidirectional"))
    )
    (net (code "216") (name "unconnected-(D-Pad9)") (class "Default")
      (node (ref "D") (pin "9") (pinfunction "9_9") (pintype "bidirectional"))
    )
    (net (code "217") (name "unconnected-(D-Pad10)") (class "Default")
      (node (ref "D") (pin "10") (pinfunction "10_10") (pintype "bidirectional"))
    )
    (net (code "218") (name "unconnected-(D-Pad11)") (class "Default")
      (node (ref "D") (pin "11") (pinfunction "11_11") (pintype "bidirectional"))
    )
    (net (code "219") (name "unconnected-(D-Pad12)") (class "Default")
      (node (ref "D") (pin "12") (pinfunction "12_12") (pintype "bidirectional"))
    )
    (net (code "220") (name "unconnected-(D-Pad13)") (class "Default")
      (node (ref "D") (pin "13") (pinfunction "13_13") (pintype "bidirectional"))
    )
    (net (code "221") (name "unconnected-(D-Pad14)") (class "Default")
      (node (ref "D") (pin "14") (pinfunction "14_14") (pintype "bidirectional"))
    )
    (net (code "222") (name "unconnected-(D-Pad15)") (class "Default")
      (node (ref "D") (pin "15") (pinfunction "15_15") (pintype "bidirectional"))
    )
    (net (code "223") (name "unconnected-(D-Pad16)") (class "Default")
      (node (ref "D") (pin "16") (pinfunction "16_16") (pintype "bidirectional"))
    )
    (net (code "224") (name "unconnected-(D-Pad17)") (class "Default")
      (node (ref "D") (pin "17") (pinfunction "17_17") (pintype "bidirectional"))
    )
    (net (code "225") (name "unconnected-(D-Pad18)") (class "Default")
      (node (ref "D") (pin "18") (pinfunction "18_18") (pintype "bidirectional"))
    )
    (net (code "226") (name "unconnected-(D-Pad19)") (class "Default")
      (node (ref "D") (pin "19") (pinfunction "19_19") (pintype "bidirectional"))
    )
    (net (code "227") (name "unconnected-(D-Pad20)") (class "Default")
      (node (ref "D") (pin "20") (pinfunction "20_20") (pintype "bidirectional"))
    )
    (net (code "228") (name "unconnected-(D-Pad21)") (class "Default")
      (node (ref "D") (pin "21") (pinfunction "21_21") (pintype "bidirectional"))
    )
    (net (code "229") (name "unconnected-(D-Pad22)") (class "Default")
      (node (ref "D") (pin "22") (pinfunction "22_22") (pintype "bidirectional"))
    )
    (net (code "230") (name "unconnected-(D-Pad23)") (class "Default")
      (node (ref "D") (pin "23") (pinfunction "23_23") (pintype "bidirectional"))
    )
    (net (code "231") (name "unconnected-(D-Pad24)") (class "Default")
      (node (ref "D") (pin "24") (pinfunction "24_24") (pintype "bidirectional"))
    )
    (net (code "232") (name "unconnected-(D-Pad25)") (class "Default")
      (node (ref "D") (pin "25") (pinfunction "25_25") (pintype "bidirectional"))
    )
    (net (code "233") (name "unconnected-(D-Pad26)") (class "Default")
      (node (ref "D") (pin "26") (pinfunction "26_26") (pintype "bidirectional"))
    )
    (net (code "234") (name "unconnected-(D-Pad27)") (class "Default")
      (node (ref "D") (pin "27") (pinfunction "27_27") (pintype "bidirectional"))
    )
    (net (code "235") (name "unconnected-(D-Pad28)") (class "Default")
      (node (ref "D") (pin "28") (pinfunction "28_28") (pintype "bidirectional"))
    )
    (net (code "236") (name "unconnected-(D-Pad29)") (class "Default")
      (node (ref "D") (pin "29") (pinfunction "29_29") (pintype "bidirectional"))
    )
    (net (code "237") (name "unconnected-(D-Pad30)") (class "Default")
      (node (ref "D") (pin "30") (pinfunction "30_30") (pintype "bidirectional"))
    )
    (net (code "238") (name "unconnected-(D-Pad31)") (class "Default")
      (node (ref "D") (pin "31") (pinfunction "31_31") (pintype "bidirectional"))
    )
    (net (code "239") (name "unconnected-(D-Pad32)") (class "Default")
      (node (ref "D") (pin "32") (pinfunction "32_32") (pintype "bidirectional"))
    )
    (net (code "240") (name "unconnected-(D-Pad33)") (class "Default")
      (node (ref "D") (pin "33") (pinfunction "33_33") (pintype "bidirectional"))
    )
    (net (code "241") (name "unconnected-(D-Pad37)") (class "Default")
      (node (ref "D") (pin "37") (pinfunction "37_37") (pintype "bidirectional"))
    )
    (net (code "242") (name "unconnected-(D-Pad38)") (class "Default")
      (node (ref "D") (pin "38") (pinfunction "38_38") (pintype "bidirectional"))
    )
    (net (code "243") (name "unconnected-(D-Pad39)") (class "Default")
      (node (ref "D") (pin "39") (pinfunction "39_39") (pintype "bidirectional"))
    )
    (net (code "244") (name "unconnected-(D-Pad40)") (class "Default")
      (node (ref "D") (pin "40") (pinfunction "40_40") (pintype "bidirectional"))
    )
    (net (code "245") (name "unconnected-(D-Pad41)") (class "Default")
      (node (ref "D") (pin "41") (pinfunction "41_41") (pintype "bidirectional"))
    )
    (net (code "246") (name "unconnected-(D-Pad42)") (class "Default")
      (node (ref "D") (pin "42") (pinfunction "42_42") (pintype "bidirectional"))
    )
    (net (code "247") (name "unconnected-(D-Pad43)") (class "Default")
      (node (ref "D") (pin "43") (pinfunction "43_43") (pintype "bidirectional"))
    )
    (net (code "248") (name "unconnected-(D-Pad44)") (class "Default")
      (node (ref "D") (pin "44") (pinfunction "44_44") (pintype "bidirectional"))
    )
    (net (code "249") (name "unconnected-(D-Pad45)") (class "Default")
      (node (ref "D") (pin "45") (pinfunction "45_45") (pintype "bidirectional"))
    )
    (net (code "250") (name "unconnected-(D-Pad46)") (class "Default")
      (node (ref "D") (pin "46") (pinfunction "46_46") (pintype "bidirectional"))
    )
    (net (code "251") (name "unconnected-(D-Pad47)") (class "Default")
      (node (ref "D") (pin "47") (pinfunction "47_47") (pintype "bidirectional"))
    )
    (net (code "252") (name "unconnected-(D-Pad48)") (class "Default")
      (node (ref "D") (pin "48") (pinfunction "48_48") (pintype "bidirectional"))
    )
    (net (code "253") (name "unconnected-(D-Pad49)") (class "Default")
      (node (ref "D") (pin "49") (pinfunction "49_49") (pintype "bidirectional"))
    )
    (net (code "254") (name "unconnected-(D-Pad50)") (class "Default")
      (node (ref "D") (pin "50") (pinfunction "50_50") (pintype "bidirectional"))
    )
    (net (code "255") (name "unconnected-(D-Pad51)") (class "Default")
      (node (ref "D") (pin "51") (pinfunction "51_51") (pintype "bidirectional"))
    )
    (net (code "256") (name "unconnected-(D-Pad52)") (class "Default")
      (node (ref "D") (pin "52") (pinfunction "52_52") (pintype "bidirectional"))
    )
    (net (code "257") (name "unconnected-(D-Pad53)") (class "Default")
      (node (ref "D") (pin "53") (pinfunction "53_53") (pintype "bidirectional"))
    )
    (net (code "258") (name "unconnected-(D-Pad54)") (class "Default")
      (node (ref "D") (pin "54") (pinfunction "54_54") (pintype "bidirectional"))
    )
    (net (code "259") (name "unconnected-(D-Pad55)") (class "Default")
      (node (ref "D") (pin "55") (pinfunction "55_55") (pintype "bidirectional"))
    )
    (net (code "260") (name "unconnected-(D-Pad56)") (class "Default")
      (node (ref "D") (pin "56") (pinfunction "56_56") (pintype "bidirectional"))
    )
    (net (code "261") (name "unconnected-(D-Pad57)") (class "Default")
      (node (ref "D") (pin "57") (pinfunction "57_57") (pintype "bidirectional"))
    )
    (net (code "262") (name "unconnected-(D-Pad58)") (class "Default")
      (node (ref "D") (pin "58") (pinfunction "58_58") (pintype "bidirectional"))
    )
    (net (code "263") (name "unconnected-(D-Pad59)") (class "Default")
      (node (ref "D") (pin "59") (pinfunction "59_59") (pintype "bidirectional"))
    )
    (net (code "264") (name "unconnected-(D-Pad60)") (class "Default")
      (node (ref "D") (pin "60") (pinfunction "60_60") (pintype "bidirectional"))
    )
    (net (code "265") (name "unconnected-(D-Pad61)") (class "Default")
      (node (ref "D") (pin "61") (pinfunction "61_61") (pintype "bidirectional"))
    )
    (net (code "266") (name "unconnected-(D-Pad62)") (class "Default")
      (node (ref "D") (pin "62") (pinfunction "62_62") (pintype "bidirectional"))
    )
    (net (code "267") (name "unconnected-(D-Pad63)") (class "Default")
      (node (ref "D") (pin "63") (pinfunction "63_63") (pintype "bidirectional"))
    )
    (net (code "268") (name "unconnected-(D-Pad64)") (class "Default")
      (node (ref "D") (pin "64") (pinfunction "64_64") (pintype "bidirectional"))
    )
    (net (code "269") (name "unconnected-(D-Pad65)") (class "Default")
      (node (ref "D") (pin "65") (pinfunction "65_65") (pintype "bidirectional"))
    )
    (net (code "270") (name "unconnected-(D-Pad66)") (class "Default")
      (node (ref "D") (pin "66") (pinfunction "66_66") (pintype "bidirectional"))
    )
    (net (code "271") (name "unconnected-(D-Pad67)") (class "Default")
      (node (ref "D") (pin "67") (pinfunction "67_67") (pintype "bidirectional"))
    )
    (net (code "272") (name "unconnected-(D-Pad68)") (class "Default")
      (node (ref "D") (pin "68") (pinfunction "68_68") (pintype "bidirectional"))
    )
  )
)
